# SCH_System.net
KiCad netlist of a schematic drawn in Altium Designer
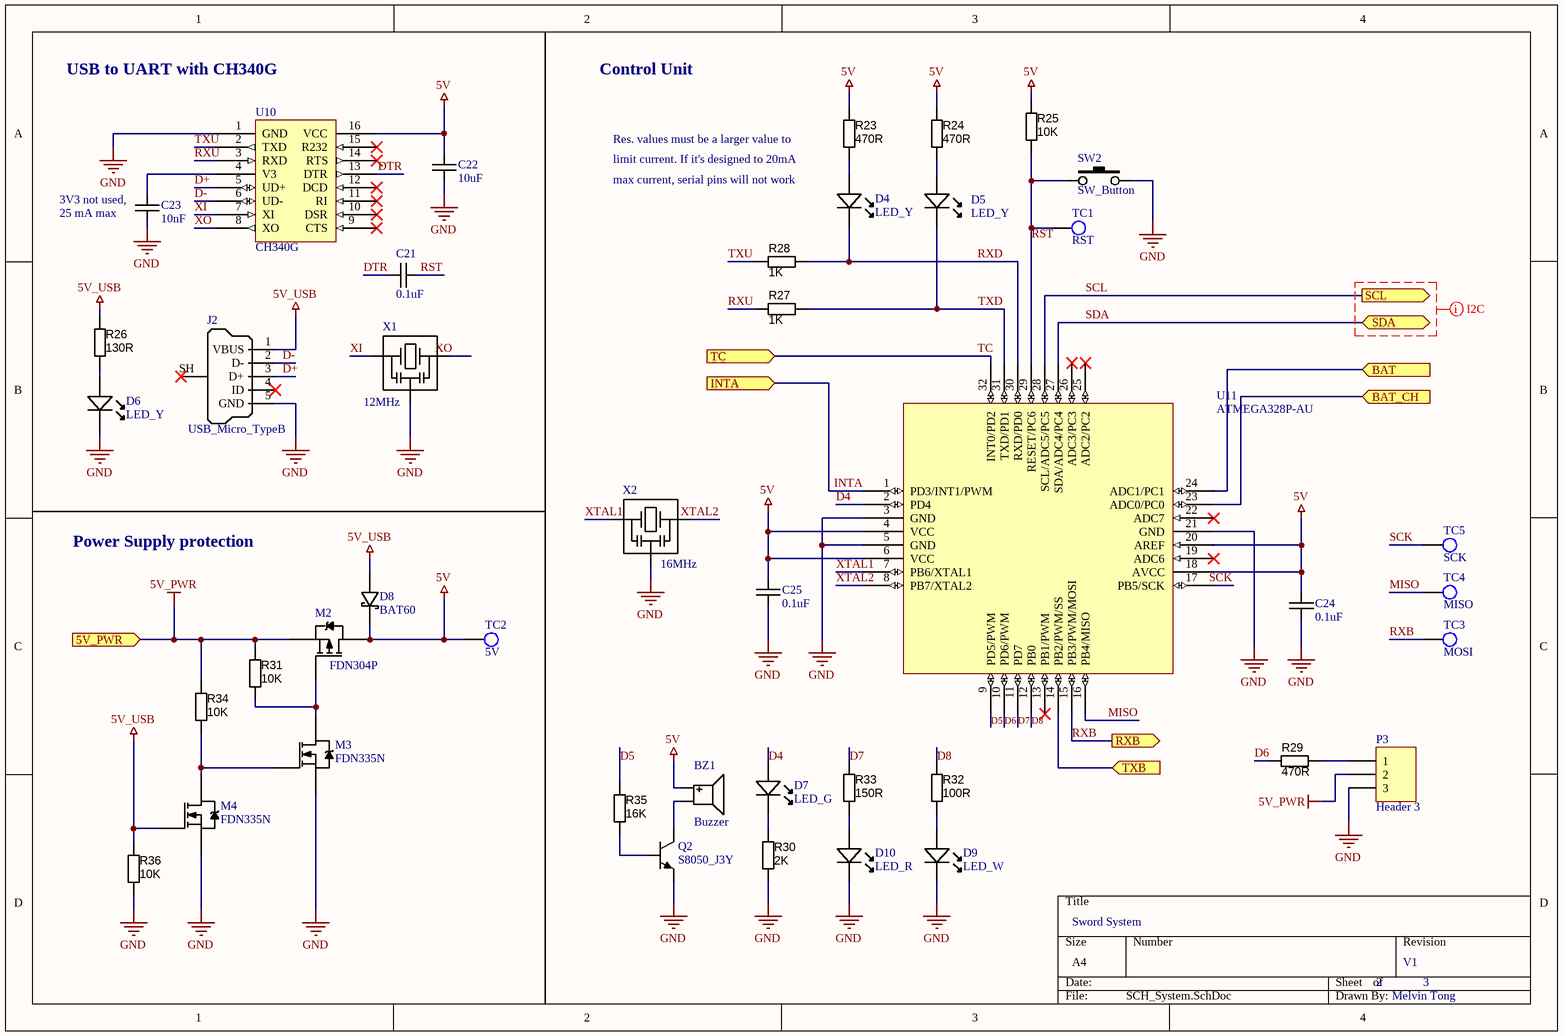
[diagram p0: SCH_System.SchDoc]

(export (version "E")
  (design (tool "Eeschema 10.0.6"))
  (components
    (comp (ref "BZ1")
      (value "Buzzer")
      (footprint "Buzzer")
      (description "Buzzer passive 5 VAC")
      (libsource (lib "Schlib_Sword") (part "Buzzer"))
    )
    (comp (ref "C21")
      (value "0.1uF")
      (footprint "CAP_0805")
      (description "SMD 0805")
      (libsource (lib "Schlib_Sword") (part "CAP_0.1uF"))
    )
    (comp (ref "C22")
      (value "10uF")
      (footprint "CAP_1206")
      (description "SMD 0805/1206")
      (libsource (lib "Schlib_Sword") (part "CAP_10uF"))
    )
    (comp (ref "C23")
      (value "10nF")
      (footprint "CAP_0805")
      (description "SMD 0805")
      (libsource (lib "Schlib_Sword") (part "CAP_10nF"))
    )
    (comp (ref "C24")
      (value "0.1uF")
      (footprint "CAP_0805")
      (description "SMD 0805")
      (libsource (lib "Schlib_Sword") (part "CAP_0.1uF"))
    )
    (comp (ref "C25")
      (value "0.1uF")
      (footprint "CAP_0805")
      (description "SMD 0805")
      (libsource (lib "Schlib_Sword") (part "CAP_0.1uF"))
    )
    (comp (ref "D4")
      (value "LED_Y")
      (footprint "LED-0603-YELLOW")
      (description "SMD_0603 2.4V")
      (libsource (lib "Schlib_Sword") (part "LED_Y"))
    )
    (comp (ref "D5")
      (value "LED_Y")
      (footprint "LED-0603-YELLOW")
      (description "SMD_0603 2.4V")
      (libsource (lib "Schlib_Sword") (part "LED_Y"))
    )
    (comp (ref "D6")
      (value "LED_Y")
      (footprint "LED-0603-YELLOW")
      (description "SMD_0603 2.4V")
      (libsource (lib "Schlib_Sword") (part "LED_Y"))
    )
    (comp (ref "D7")
      (value "LED_G")
      (footprint "LED_0805")
      (description "SMD_0805 3V")
      (libsource (lib "Schlib_Sword") (part "LED_G"))
    )
    (comp (ref "D8")
      (value "BAT60")
      (footprint "SOD323")
      (description "Schottky Diode 3A, Vf~0.24V, Vr=10V")
      (libsource (lib "Schlib_Sword") (part "BAT60"))
    )
    (comp (ref "D9")
      (value "LED_W")
      (footprint "LED_0805")
      (description "SMD_0805 3V")
      (libsource (lib "Schlib_Sword") (part "LED_W"))
    )
    (comp (ref "D10")
      (value "LED_R")
      (footprint "LED_0805")
      (description "SMD_0805 2V")
      (libsource (lib "Schlib_Sword") (part "LED_R"))
    )
    (comp (ref "J2")
      (value "USB_Micro_TypeB")
      (footprint "USB_Micro_TypeB")
      (libsource (lib "Schlib_Sword") (part "USB_Micro_TypeB"))
    )
    (comp (ref "M2") (value "FDN304P") (footprint "SOT23_213") (libsource (lib "Schlib_Sword") (part "PMOS")))
    (comp (ref "M3") (value "FDN335N") (footprint "SOT23_213") (libsource (lib "Schlib_Sword") (part "NMOS")))
    (comp (ref "M4") (value "FDN335N") (footprint "SOT23_213") (libsource (lib "Schlib_Sword") (part "NMOS")))
    (comp (ref "P3")
      (value "Header 3")
      (footprint "HDR1X3")
      (description "Header, 3-Pin")
      (fields (field (name "PUBLISHER") "Altium Limited"))
      (libsource (lib "Miscellaneous Connectors") (part "Header 3"))
    )
    (comp (ref "Q2")
      (value "S8050_J3Y")
      (footprint "SOT23_213")
      (libsource (lib "Schlib_Sword") (part "NPN"))
    )
    (comp (ref "R23")
      (value "470R")
      (footprint "RESC3216X70N")
      (description "Resistor SMD, 1206")
      (libsource (lib "Schlib_Sword") (part "RES_470R"))
    )
    (comp (ref "R24")
      (value "470R")
      (footprint "RESC3216X70N")
      (description "Resistor SMD, 1206")
      (libsource (lib "") (part "RES_470R_2"))
    )
    (comp (ref "R25")
      (value "10K")
      (footprint "RESC3216X70N")
      (description "Resistor SMD, 1206")
      (libsource (lib "Schlib_Sword") (part "RES_10K"))
    )
    (comp (ref "R26")
      (value "130R")
      (footprint "RESC3216X70N")
      (description "Resistor SMD, 1206")
      (libsource (lib "Schlib_Sword") (part "RES_130R"))
    )
    (comp (ref "R27")
      (value "1K")
      (footprint "RESC3216X70N")
      (description "Resistor SMD, 1206")
      (libsource (lib "Schlib_Sword") (part "RES_1K"))
    )
    (comp (ref "R28")
      (value "1K")
      (footprint "RESC3216X70N")
      (description "Resistor SMD, 1206")
      (libsource (lib "Schlib_Sword") (part "RES_1K"))
    )
    (comp (ref "R29")
      (value "470R")
      (footprint "RESC3216X70N")
      (description "Resistor SMD, 1206")
      (libsource (lib "") (part "RES_470R_1"))
    )
    (comp (ref "R30")
      (value "2K")
      (footprint "RESC3216X70N")
      (description "Resistor SMD, 1206")
      (libsource (lib "Schlib_Sword") (part "RES_2K"))
    )
    (comp (ref "R31")
      (value "10K")
      (footprint "RESC3216X70N")
      (description "Resistor SMD, 1206")
      (libsource (lib "Schlib_Sword") (part "RES_10K"))
    )
    (comp (ref "R32")
      (value "100R")
      (footprint "RESC3216X70N")
      (description "Resistor SMD, 1206")
      (libsource (lib "Schlib_Sword") (part "RES_100R"))
    )
    (comp (ref "R33")
      (value "150R")
      (footprint "RESC3216X70N")
      (description "Resistor SMD, 1206")
      (libsource (lib "Schlib_Sword") (part "RES_150R"))
    )
    (comp (ref "R34")
      (value "10K")
      (footprint "RESC3216X70N")
      (description "Resistor SMD, 1206")
      (libsource (lib "Schlib_Sword") (part "RES_10K"))
    )
    (comp (ref "R35")
      (value "16K")
      (footprint "RESC3216X70N")
      (description "Resistor SMD, 1206")
      (libsource (lib "Schlib_Sword") (part "RES_16K"))
    )
    (comp (ref "R36")
      (value "10K")
      (footprint "RESC3216X70N")
      (description "Resistor SMD, 1206")
      (libsource (lib "Schlib_Sword") (part "RES_10K"))
    )
    (comp (ref "SW2")
      (value "SW_Button")
      (footprint "Button_4x4x1.5")
      (libsource (lib "Schlib_Sword") (part "SW_Button"))
    )
    (comp (ref "TC1") (value "RST") (footprint "TP_15") (libsource (lib "Schlib_Sword") (part "TESTCONN")))
    (comp (ref "TC2") (value "5V") (footprint "TP_15") (libsource (lib "Schlib_Sword") (part "TESTCONN")))
    (comp (ref "TC3") (value "MOSI") (footprint "TP_15") (libsource (lib "Schlib_Sword") (part "TESTCONN")))
    (comp (ref "TC4") (value "MISO") (footprint "TP_15") (libsource (lib "Schlib_Sword") (part "TESTCONN")))
    (comp (ref "TC5") (value "SCK") (footprint "TP_15") (libsource (lib "Schlib_Sword") (part "TESTCONN")))
    (comp (ref "U10") (value "CH340G") (footprint "CH340G") (libsource (lib "Schlib_Sword") (part "CH340G")))
    (comp (ref "U11")
      (value "ATMEGA328P-AU")
      (footprint "ATMEGA328P-AU")
      (libsource (lib "Schlib_Sword") (part "ATMEGA328P-AU"))
    )
    (comp (ref "X1")
      (value "12MHz")
      (footprint "XTAL_3.2x1.6")
      (description "Crystal Oscillator")
      (libsource (lib "Schlib_Sword") (part "12MHz"))
    )
    (comp (ref "X2")
      (value "16MHz")
      (footprint "XTAL_16MHz")
      (description "Crystal Oscillator")
      (libsource (lib "Schlib_Sword") (part "16MHz"))
    )
  )
  (nets
    (net (code "1") (name "/BAT") (class "Default")
      (node (ref "U11") (pin "24") (pinfunction "ADC1/PC1_24") (pintype "bidirectional"))
    )
    (net (code "2") (name "/BAT_CH") (class "Default")
      (node (ref "U11") (pin "23") (pinfunction "ADC0/PC0_23") (pintype "bidirectional"))
    )
    (net (code "3") (name "/D+") (class "Default")
      (node (ref "J2") (pin "3") (pinfunction "D+_3") (pintype "passive"))
      (node (ref "U10") (pin "5") (pinfunction "UD+_5") (pintype "bidirectional"))
    )
    (net (code "4") (name "/D-") (class "Default")
      (node (ref "J2") (pin "2") (pinfunction "D-_2") (pintype "passive"))
      (node (ref "U10") (pin "6") (pinfunction "UD-_6") (pintype "bidirectional"))
    )
    (net (code "5") (name "/D4") (class "Default")
      (node (ref "D7") (pin "A") (pinfunction "A_A") (pintype "passive"))
      (node (ref "U11") (pin "2") (pinfunction "PD4_2") (pintype "bidirectional"))
    )
    (net (code "6") (name "/D5") (class "Default")
      (node (ref "R35") (pin "1") (pinfunction "1_1") (pintype "passive"))
      (node (ref "U11") (pin "9") (pinfunction "PD5/PWM_9") (pintype "bidirectional"))
    )
    (net (code "7") (name "/D6") (class "Default")
      (node (ref "R29") (pin "2") (pinfunction "2_2") (pintype "passive"))
      (node (ref "U11") (pin "10") (pinfunction "PD6/PWM_10") (pintype "bidirectional"))
    )
    (net (code "8") (name "/D7") (class "Default")
      (node (ref "R33") (pin "1") (pinfunction "1_1") (pintype "passive"))
      (node (ref "U11") (pin "11") (pinfunction "PD7_11") (pintype "bidirectional"))
    )
    (net (code "9") (name "/D8") (class "Default")
      (node (ref "R32") (pin "2") (pinfunction "2_2") (pintype "passive"))
      (node (ref "U11") (pin "12") (pinfunction "PB0_12") (pintype "bidirectional"))
    )
    (net (code "10") (name "/DTR") (class "Default")
      (node (ref "C21") (pin "1") (pintype "passive"))
      (node (ref "U10") (pin "13") (pinfunction "DTR_13") (pintype "output"))
    )
    (net (code "11") (name "/INTA") (class "Default")
      (node (ref "U11") (pin "1") (pinfunction "PD3/INT1/PWM_1") (pintype "bidirectional"))
    )
    (net (code "12") (name "/MISO") (class "Default")
      (node (ref "TC4") (pin "1") (pinfunction "1_1") (pintype "passive"))
      (node (ref "U11") (pin "16") (pinfunction "PB4/MISO_16") (pintype "bidirectional"))
    )
    (net (code "13") (name "/RST") (class "Default")
      (node (ref "C21") (pin "2") (pintype "passive"))
      (node (ref "R25") (pin "2") (pinfunction "2_2") (pintype "passive"))
      (node (ref "SW2") (pin "1") (pintype "passive"))
      (node (ref "TC1") (pin "1") (pinfunction "1_1") (pintype "passive"))
      (node (ref "U11") (pin "29") (pinfunction "RESET/PC6_29") (pintype "bidirectional"))
    )
    (net (code "14") (name "/RXB") (class "Default")
      (node (ref "TC3") (pin "1") (pinfunction "1_1") (pintype "passive"))
      (node (ref "U11") (pin "15") (pinfunction "PB3/PWM/MOSI_15") (pintype "bidirectional"))
    )
    (net (code "15") (name "/RXD") (class "Default")
      (node (ref "D4") (pin "K") (pinfunction "K_K") (pintype "passive"))
      (node (ref "R28") (pin "2") (pinfunction "2_2") (pintype "passive"))
      (node (ref "U11") (pin "30") (pinfunction "RXD/PD0_30") (pintype "bidirectional"))
    )
    (net (code "16") (name "/RXU") (class "Default")
      (node (ref "R27") (pin "1") (pinfunction "1_1") (pintype "passive"))
      (node (ref "U10") (pin "3") (pinfunction "RXD_3") (pintype "input"))
    )
    (net (code "17") (name "/SCK") (class "Default")
      (node (ref "TC5") (pin "1") (pinfunction "1_1") (pintype "passive"))
      (node (ref "U11") (pin "17") (pinfunction "PB5/SCK_17") (pintype "bidirectional"))
    )
    (net (code "18") (name "/SCL") (class "Default")
      (node (ref "U11") (pin "28") (pinfunction "SCL/ADC5/PC5_28") (pintype "bidirectional"))
    )
    (net (code "19") (name "/SDA") (class "Default")
      (node (ref "U11") (pin "27") (pinfunction "SDA/ADC4/PC4_27") (pintype "bidirectional"))
    )
    (net (code "20") (name "/TC") (class "Default")
      (node (ref "U11") (pin "32") (pinfunction "INT0/PD2_32") (pintype "bidirectional"))
    )
    (net (code "21") (name "/TXB") (class "Default")
      (node (ref "U11") (pin "14") (pinfunction "PB2/PWM/SS_14") (pintype "bidirectional"))
    )
    (net (code "22") (name "/TXD") (class "Default")
      (node (ref "D5") (pin "K") (pinfunction "K_K") (pintype "passive"))
      (node (ref "R27") (pin "2") (pinfunction "2_2") (pintype "passive"))
      (node (ref "U11") (pin "31") (pinfunction "TXD/PD1_31") (pintype "bidirectional"))
    )
    (net (code "23") (name "/TXU") (class "Default")
      (node (ref "R28") (pin "1") (pinfunction "1_1") (pintype "passive"))
      (node (ref "U10") (pin "2") (pinfunction "TXD_2") (pintype "output"))
    )
    (net (code "24") (name "/XI") (class "Default")
      (node (ref "U10") (pin "7") (pinfunction "XI_7") (pintype "input"))
      (node (ref "X1") (pin "1") (pinfunction "IN_1") (pintype "passive"))
    )
    (net (code "25") (name "/XO") (class "Default")
      (node (ref "U10") (pin "8") (pinfunction "XO_8") (pintype "output"))
      (node (ref "X1") (pin "3") (pinfunction "OUT_3") (pintype "passive"))
    )
    (net (code "26") (name "/XTAL1") (class "Default")
      (node (ref "U11") (pin "7") (pinfunction "PB6/XTAL1_7") (pintype "bidirectional"))
      (node (ref "X2") (pin "1") (pinfunction "IN_1") (pintype "passive"))
    )
    (net (code "27") (name "/XTAL2") (class "Default")
      (node (ref "U11") (pin "8") (pinfunction "PB7/XTAL2_8") (pintype "bidirectional"))
      (node (ref "X2") (pin "3") (pinfunction "OUT_3") (pintype "passive"))
    )
    (net (code "28") (name "5V") (class "Default")
      (node (ref "BZ1") (pin "1") (pinfunction "Positive_1") (pintype "passive"))
      (node (ref "C22") (pin "1") (pintype "passive"))
      (node (ref "C24") (pin "2") (pintype "passive"))
      (node (ref "C25") (pin "2") (pintype "passive"))
      (node (ref "D8") (pin "K") (pinfunction "K_K") (pintype "passive"))
      (node (ref "M2") (pin "3") (pinfunction "D_3") (pintype "passive"))
      (node (ref "R23") (pin "2") (pinfunction "2_2") (pintype "passive"))
      (node (ref "R24") (pin "1") (pinfunction "1_1") (pintype "passive"))
      (node (ref "R25") (pin "1") (pinfunction "1_1") (pintype "passive"))
      (node (ref "TC2") (pin "1") (pinfunction "1_1") (pintype "passive"))
      (node (ref "U10") (pin "16") (pinfunction "VCC_16") (pintype "power_in"))
      (node (ref "U11") (pin "18") (pinfunction "AVCC_18") (pintype "power_in"))
      (node (ref "U11") (pin "20") (pinfunction "AREF_20") (pintype "input"))
      (node (ref "U11") (pin "4") (pinfunction "VCC_4") (pintype "power_in"))
      (node (ref "U11") (pin "6") (pinfunction "VCC_6") (pintype "power_in"))
    )
    (net (code "29") (name "5V_PWR") (class "Default")
      (node (ref "M2") (pin "2") (pinfunction "S_2") (pintype "passive"))
      (node (ref "P3") (pin "2") (pinfunction "2_2") (pintype "passive"))
      (node (ref "R31") (pin "1") (pinfunction "1_1") (pintype "passive"))
      (node (ref "R34") (pin "1") (pinfunction "1_1") (pintype "passive"))
    )
    (net (code "30") (name "5V_USB") (class "Default")
      (node (ref "D8") (pin "A") (pinfunction "A_A") (pintype "passive"))
      (node (ref "J2") (pin "1") (pinfunction "VBUS_1") (pintype "passive"))
      (node (ref "M4") (pin "1") (pinfunction "G_1") (pintype "passive"))
      (node (ref "R26") (pin "2") (pinfunction "2_2") (pintype "passive"))
      (node (ref "R36") (pin "1") (pinfunction "1_1") (pintype "passive"))
    )
    (net (code "31") (name "GND") (class "Default")
      (node (ref "C22") (pin "2") (pintype "passive"))
      (node (ref "C23") (pin "2") (pintype "passive"))
      (node (ref "C24") (pin "1") (pintype "passive"))
      (node (ref "C25") (pin "1") (pintype "passive"))
      (node (ref "D10") (pin "K") (pinfunction "K_K") (pintype "passive"))
      (node (ref "D6") (pin "K") (pinfunction "K_K") (pintype "passive"))
      (node (ref "D9") (pin "K") (pinfunction "K_K") (pintype "passive"))
      (node (ref "J2") (pin "5") (pinfunction "GND_5") (pintype "passive"))
      (node (ref "M3") (pin "2") (pinfunction "S_2") (pintype "passive"))
      (node (ref "M4") (pin "2") (pinfunction "S_2") (pintype "passive"))
      (node (ref "P3") (pin "3") (pinfunction "3_3") (pintype "passive"))
      (node (ref "Q2") (pin "2") (pinfunction "E_2") (pintype "passive"))
      (node (ref "R30") (pin "2") (pinfunction "2_2") (pintype "passive"))
      (node (ref "R36") (pin "2") (pinfunction "2_2") (pintype "passive"))
      (node (ref "SW2") (pin "2") (pintype "passive"))
      (node (ref "U10") (pin "1") (pinfunction "GND_1") (pintype "power_in"))
      (node (ref "U11") (pin "21") (pinfunction "GND_21") (pintype "power_in"))
      (node (ref "U11") (pin "3") (pinfunction "GND_3") (pintype "power_in"))
      (node (ref "U11") (pin "5") (pinfunction "GND_5") (pintype "power_in"))
      (node (ref "X1") (pin "2") (pinfunction "GND_2") (pintype "passive"))
      (node (ref "X2") (pin "2") (pinfunction "GND_2") (pintype "passive"))
    )
    (net (code "32") (name "Net-(BZ1-Negative)") (class "Default")
      (node (ref "BZ1") (pin "2") (pinfunction "Negative_2") (pintype "passive"))
      (node (ref "Q2") (pin "3") (pinfunction "C_3") (pintype "passive"))
    )
    (net (code "33") (name "Net-(D4-PadA)") (class "Default")
      (node (ref "D4") (pin "A") (pinfunction "A_A") (pintype "passive"))
      (node (ref "R23") (pin "1") (pinfunction "1_1") (pintype "passive"))
    )
    (net (code "34") (name "Net-(D5-PadA)") (class "Default")
      (node (ref "D5") (pin "A") (pinfunction "A_A") (pintype "passive"))
      (node (ref "R24") (pin "2") (pinfunction "2_2") (pintype "passive"))
    )
    (net (code "35") (name "Net-(D6-PadA)") (class "Default")
      (node (ref "D6") (pin "A") (pinfunction "A_A") (pintype "passive"))
      (node (ref "R26") (pin "1") (pinfunction "1_1") (pintype "passive"))
    )
    (net (code "36") (name "Net-(D7-PadK)") (class "Default")
      (node (ref "D7") (pin "K") (pinfunction "K_K") (pintype "passive"))
      (node (ref "R30") (pin "1") (pinfunction "1_1") (pintype "passive"))
    )
    (net (code "37") (name "Net-(D9-PadA)") (class "Default")
      (node (ref "D9") (pin "A") (pinfunction "A_A") (pintype "passive"))
      (node (ref "R32") (pin "1") (pinfunction "1_1") (pintype "passive"))
    )
    (net (code "38") (name "Net-(D10-PadA)") (class "Default")
      (node (ref "D10") (pin "A") (pinfunction "A_A") (pintype "passive"))
      (node (ref "R33") (pin "2") (pinfunction "2_2") (pintype "passive"))
    )
    (net (code "39") (name "Net-(M2-G)") (class "Default")
      (node (ref "M2") (pin "1") (pinfunction "G_1") (pintype "passive"))
      (node (ref "M3") (pin "3") (pinfunction "D_3") (pintype "passive"))
      (node (ref "R31") (pin "2") (pinfunction "2_2") (pintype "passive"))
    )
    (net (code "40") (name "Net-(M3-G)") (class "Default")
      (node (ref "M3") (pin "1") (pinfunction "G_1") (pintype "passive"))
      (node (ref "M4") (pin "3") (pinfunction "D_3") (pintype "passive"))
      (node (ref "R34") (pin "2") (pinfunction "2_2") (pintype "passive"))
    )
    (net (code "41") (name "Net-(P3-Pad1)") (class "Default")
      (node (ref "P3") (pin "1") (pinfunction "1_1") (pintype "passive"))
      (node (ref "R29") (pin "1") (pinfunction "1_1") (pintype "passive"))
    )
    (net (code "42") (name "Net-(Q2-B)") (class "Default")
      (node (ref "Q2") (pin "1") (pinfunction "B_1") (pintype "passive"))
      (node (ref "R35") (pin "2") (pinfunction "2_2") (pintype "passive"))
    )
    (net (code "43") (name "Net-(U10-V3)") (class "Default")
      (node (ref "C23") (pin "1") (pintype "passive"))
      (node (ref "U10") (pin "4") (pinfunction "V3_4") (pintype "power_in"))
    )
    (net (code "44") (name "unconnected-(J2-ID-Pad4)") (class "Default")
      (node (ref "J2") (pin "4") (pinfunction "ID_4") (pintype "passive+no_connect"))
    )
    (net (code "45") (name "unconnected-(J2-Shell-PadSH)") (class "Default")
      (node (ref "J2") (pin "SH") (pinfunction "Shell_SH") (pintype "passive+no_connect"))
    )
    (net (code "46") (name "unconnected-(U10-CTS-Pad9)") (class "Default")
      (node (ref "U10") (pin "9") (pinfunction "CTS_9") (pintype "input+no_connect"))
    )
    (net (code "47") (name "unconnected-(U10-DCD-Pad12)") (class "Default")
      (node (ref "U10") (pin "12") (pinfunction "DCD_12") (pintype "input+no_connect"))
    )
    (net (code "48") (name "unconnected-(U10-DSR-Pad10)") (class "Default")
      (node (ref "U10") (pin "10") (pinfunction "DSR_10") (pintype "input+no_connect"))
    )
    (net (code "49") (name "unconnected-(U10-R232-Pad15)") (class "Default")
      (node (ref "U10") (pin "15") (pinfunction "R232_15") (pintype "input+no_connect"))
    )
    (net (code "50") (name "unconnected-(U10-RI-Pad11)") (class "Default")
      (node (ref "U10") (pin "11") (pinfunction "RI_11") (pintype "input+no_connect"))
    )
    (net (code "51") (name "unconnected-(U10-RTS-Pad14)") (class "Default")
      (node (ref "U10") (pin "14") (pinfunction "RTS_14") (pintype "output+no_connect"))
    )
    (net (code "52") (name "unconnected-(U11-ADC2{slash}PC2-Pad25)") (class "Default")
      (node (ref "U11") (pin "25") (pinfunction "ADC2/PC2_25") (pintype "bidirectional+no_connect"))
    )
    (net (code "53") (name "unconnected-(U11-ADC3{slash}PC3-Pad26)") (class "Default")
      (node (ref "U11") (pin "26") (pinfunction "ADC3/PC3_26") (pintype "bidirectional+no_connect"))
    )
    (net (code "54") (name "unconnected-(U11-ADC6-Pad19)") (class "Default")
      (node (ref "U11") (pin "19") (pinfunction "ADC6_19") (pintype "input+no_connect"))
    )
    (net (code "55") (name "unconnected-(U11-ADC7-Pad22)") (class "Default")
      (node (ref "U11") (pin "22") (pinfunction "ADC7_22") (pintype "input+no_connect"))
    )
    (net (code "56") (name "unconnected-(U11-PB1{slash}PWM-Pad13)") (class "Default")
      (node (ref "U11") (pin "13") (pinfunction "PB1/PWM_13") (pintype "bidirectional+no_connect"))
    )
  )
)
